# Devi_Lite.net
KiCad netlist of a schematic drawn in EAGLE
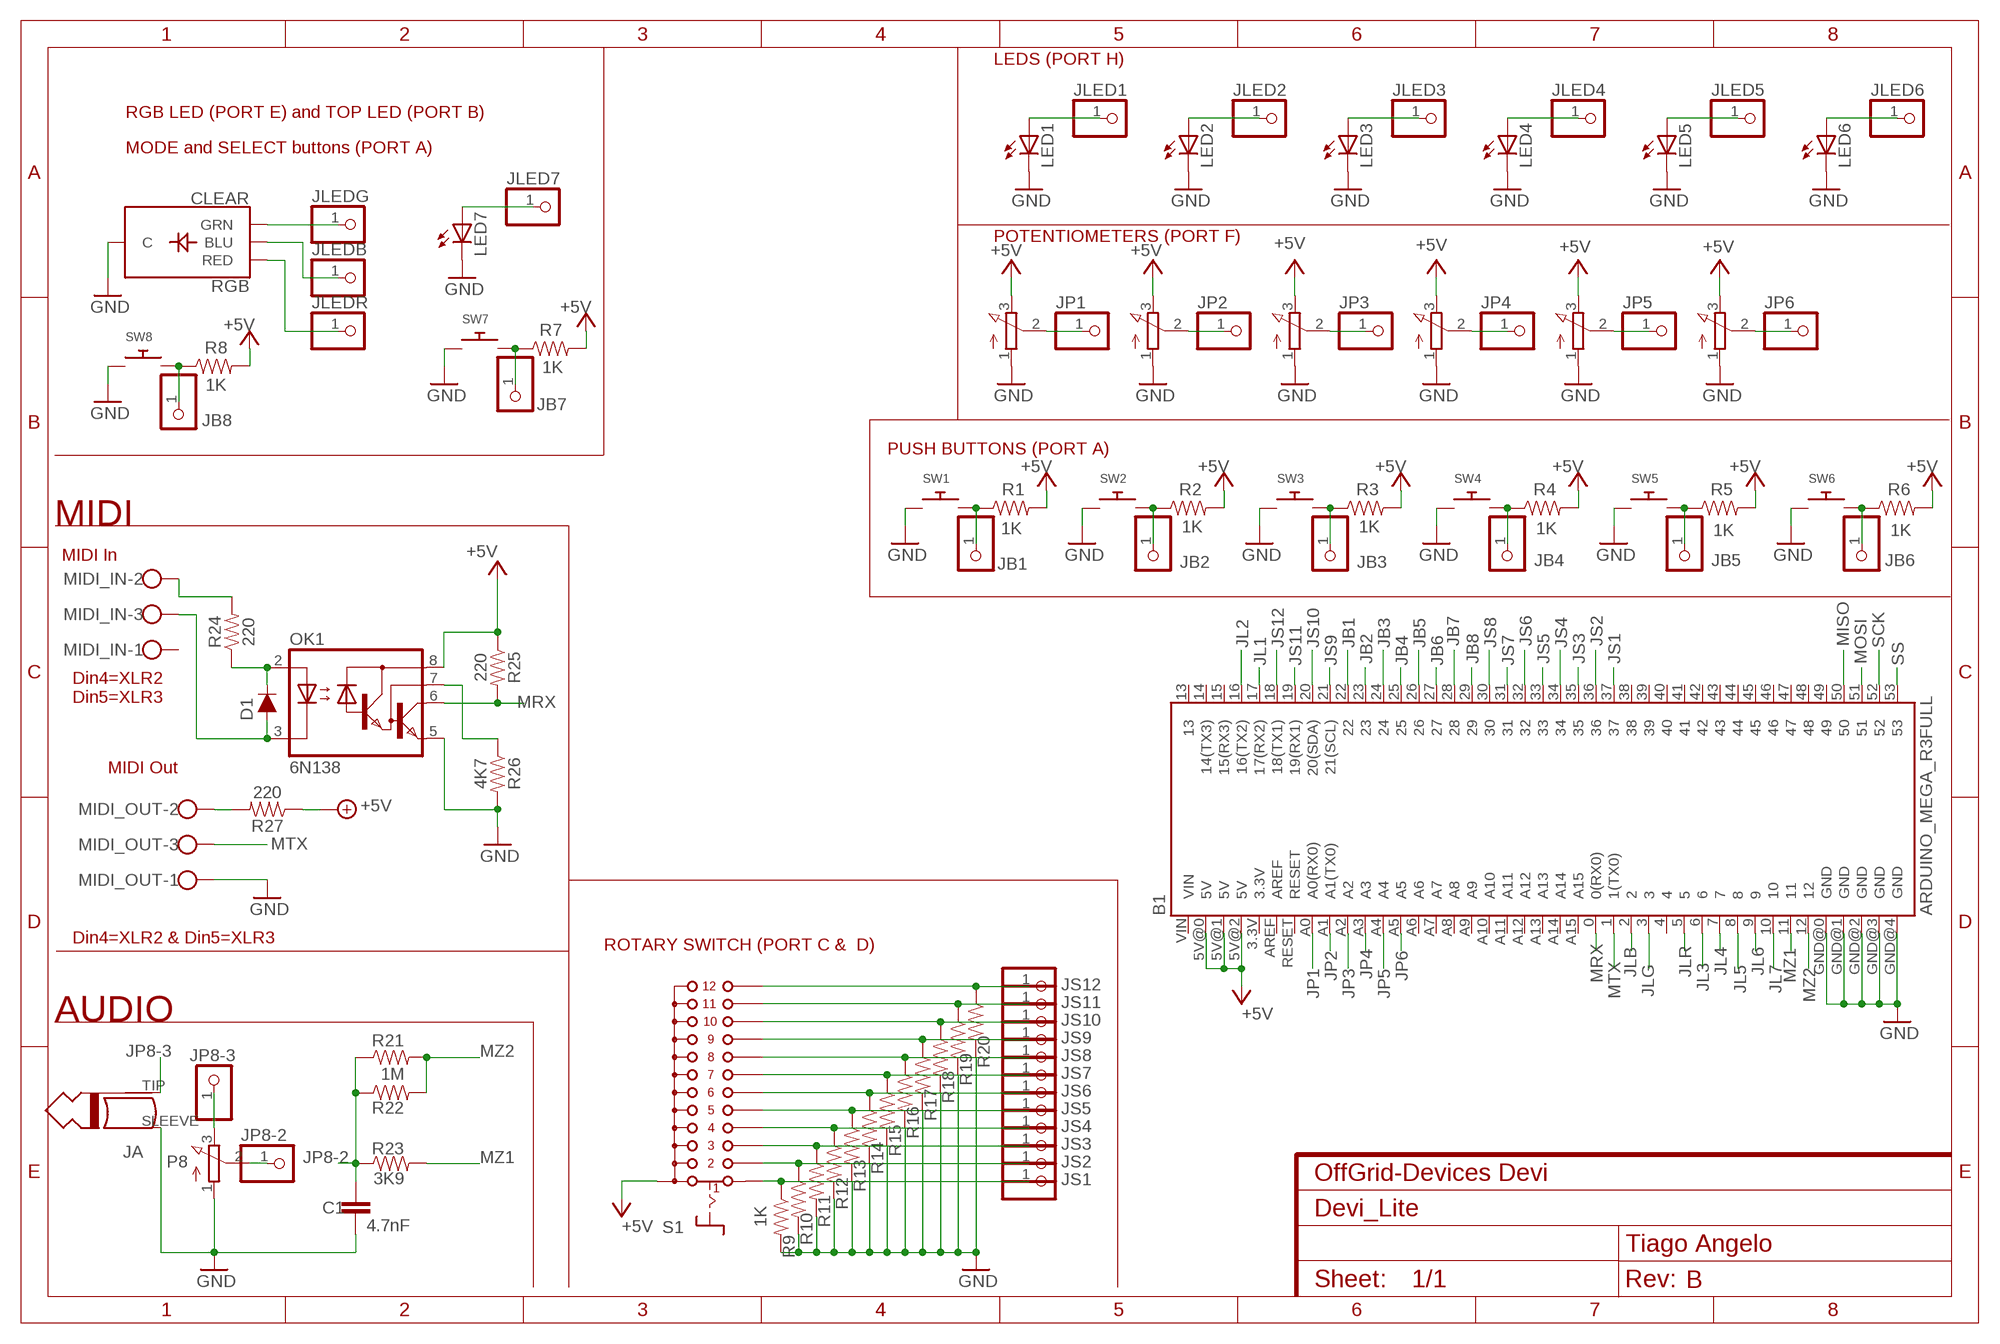
[diagram p0: schematic, sheet 1]

(export (version "E")
  (design (tool "Eeschema 10.0.6"))
  (components
    (comp (ref "B1")
      (value "ARDUINO_MEGA_R3FULL")
      (footprint "eagle-import:ARDUINO_MEGA")
      (libsource (lib "eagle-import") (part "ARDUINO_MEGA_R3FULL"))
    )
    (comp (ref "C1")
      (value "4.7nF")
      (footprint "eagle-import:C050-025X075")
      (libsource (lib "eagle-import") (part "C-EU050-025X075"))
    )
    (comp (ref "D1")
      (value "200mA/100V/1V")
      (footprint "eagle-import:DIODE-1N4148")
      (libsource (lib "eagle-import") (part "DIODE-1N4148"))
    )
    (comp (ref "JA")
      (value "MONO_PLUG")
      (footprint "eagle-import:TWO_PADS")
      (libsource (lib "eagle-import") (part "MONO_PLUG"))
    )
    (comp (ref "JB1")
      (value "PINHD-1X1CB")
      (footprint "eagle-import:1X01-CLEANBIG")
      (libsource (lib "eagle-import") (part "PINHD-1X1CB"))
    )
    (comp (ref "JB2")
      (value "PINHD-1X1CB")
      (footprint "eagle-import:1X01-CLEANBIG")
      (libsource (lib "eagle-import") (part "PINHD-1X1CB"))
    )
    (comp (ref "JB3")
      (value "PINHD-1X1CB")
      (footprint "eagle-import:1X01-CLEANBIG")
      (libsource (lib "eagle-import") (part "PINHD-1X1CB"))
    )
    (comp (ref "JB4")
      (value "PINHD-1X1CB")
      (footprint "eagle-import:1X01-CLEANBIG")
      (libsource (lib "eagle-import") (part "PINHD-1X1CB"))
    )
    (comp (ref "JB5")
      (value "PINHD-1X1CB")
      (footprint "eagle-import:1X01-CLEANBIG")
      (libsource (lib "eagle-import") (part "PINHD-1X1CB"))
    )
    (comp (ref "JB6")
      (value "PINHD-1X1CB")
      (footprint "eagle-import:1X01-CLEANBIG")
      (libsource (lib "eagle-import") (part "PINHD-1X1CB"))
    )
    (comp (ref "JB7")
      (value "PINHD-1X1CB")
      (footprint "eagle-import:1X01-CLEANBIG")
      (libsource (lib "eagle-import") (part "PINHD-1X1CB"))
    )
    (comp (ref "JB8")
      (value "PINHD-1X1CB")
      (footprint "eagle-import:1X01-CLEANBIG")
      (libsource (lib "eagle-import") (part "PINHD-1X1CB"))
    )
    (comp (ref "JLED1")
      (value "PINHD-1X1CB")
      (footprint "eagle-import:1X01-CLEANBIG")
      (libsource (lib "eagle-import") (part "PINHD-1X1CB"))
    )
    (comp (ref "JLED2")
      (value "PINHD-1X1CB")
      (footprint "eagle-import:1X01-CLEANBIG")
      (libsource (lib "eagle-import") (part "PINHD-1X1CB"))
    )
    (comp (ref "JLED3")
      (value "PINHD-1X1CB")
      (footprint "eagle-import:1X01-CLEANBIG")
      (libsource (lib "eagle-import") (part "PINHD-1X1CB"))
    )
    (comp (ref "JLED4")
      (value "PINHD-1X1CB")
      (footprint "eagle-import:1X01-CLEANBIG")
      (libsource (lib "eagle-import") (part "PINHD-1X1CB"))
    )
    (comp (ref "JLED5")
      (value "PINHD-1X1CB")
      (footprint "eagle-import:1X01-CLEANBIG")
      (libsource (lib "eagle-import") (part "PINHD-1X1CB"))
    )
    (comp (ref "JLED6")
      (value "PINHD-1X1CB")
      (footprint "eagle-import:1X01-CLEANBIG")
      (libsource (lib "eagle-import") (part "PINHD-1X1CB"))
    )
    (comp (ref "JLED7")
      (value "PINHD-1X1CB")
      (footprint "eagle-import:1X01-CLEANBIG")
      (libsource (lib "eagle-import") (part "PINHD-1X1CB"))
    )
    (comp (ref "JLEDB")
      (value "PINHD-1X1CB")
      (footprint "eagle-import:1X01-CLEANBIG")
      (libsource (lib "eagle-import") (part "PINHD-1X1CB"))
    )
    (comp (ref "JLEDG")
      (value "PINHD-1X1CB")
      (footprint "eagle-import:1X01-CLEANBIG")
      (libsource (lib "eagle-import") (part "PINHD-1X1CB"))
    )
    (comp (ref "JLEDR")
      (value "PINHD-1X1CB")
      (footprint "eagle-import:1X01-CLEANBIG")
      (libsource (lib "eagle-import") (part "PINHD-1X1CB"))
    )
    (comp (ref "JP1")
      (value "PINHD-1X1CB")
      (footprint "eagle-import:1X01-CLEANBIG")
      (libsource (lib "eagle-import") (part "PINHD-1X1CB"))
    )
    (comp (ref "JP2")
      (value "PINHD-1X1CB")
      (footprint "eagle-import:1X01-CLEANBIG")
      (libsource (lib "eagle-import") (part "PINHD-1X1CB"))
    )
    (comp (ref "JP3")
      (value "PINHD-1X1CB")
      (footprint "eagle-import:1X01-CLEANBIG")
      (libsource (lib "eagle-import") (part "PINHD-1X1CB"))
    )
    (comp (ref "JP4")
      (value "PINHD-1X1CB")
      (footprint "eagle-import:1X01-CLEANBIG")
      (libsource (lib "eagle-import") (part "PINHD-1X1CB"))
    )
    (comp (ref "JP5")
      (value "PINHD-1X1CB")
      (footprint "eagle-import:1X01-CLEANBIG")
      (libsource (lib "eagle-import") (part "PINHD-1X1CB"))
    )
    (comp (ref "JP6")
      (value "PINHD-1X1CB")
      (footprint "eagle-import:1X01-CLEANBIG")
      (libsource (lib "eagle-import") (part "PINHD-1X1CB"))
    )
    (comp (ref "JP8-2")
      (value "PINHD-1X1CB")
      (footprint "eagle-import:1X01-CLEANBIG")
      (libsource (lib "eagle-import") (part "PINHD-1X1CB"))
    )
    (comp (ref "JP8-3")
      (value "PINHD-1X1CB")
      (footprint "eagle-import:1X01-CLEANBIG")
      (libsource (lib "eagle-import") (part "PINHD-1X1CB"))
    )
    (comp (ref "JS1")
      (value "PINHD-1X1CB")
      (footprint "eagle-import:1X01-CLEANBIG")
      (libsource (lib "eagle-import") (part "PINHD-1X1CB"))
    )
    (comp (ref "JS2")
      (value "PINHD-1X1CB")
      (footprint "eagle-import:1X01-CLEANBIG")
      (libsource (lib "eagle-import") (part "PINHD-1X1CB"))
    )
    (comp (ref "JS3")
      (value "PINHD-1X1CB")
      (footprint "eagle-import:1X01-CLEANBIG")
      (libsource (lib "eagle-import") (part "PINHD-1X1CB"))
    )
    (comp (ref "JS4")
      (value "PINHD-1X1CB")
      (footprint "eagle-import:1X01-CLEANBIG")
      (libsource (lib "eagle-import") (part "PINHD-1X1CB"))
    )
    (comp (ref "JS5")
      (value "PINHD-1X1CB")
      (footprint "eagle-import:1X01-CLEANBIG")
      (libsource (lib "eagle-import") (part "PINHD-1X1CB"))
    )
    (comp (ref "JS6")
      (value "PINHD-1X1CB")
      (footprint "eagle-import:1X01-CLEANBIG")
      (libsource (lib "eagle-import") (part "PINHD-1X1CB"))
    )
    (comp (ref "JS7")
      (value "PINHD-1X1CB")
      (footprint "eagle-import:1X01-CLEANBIG")
      (libsource (lib "eagle-import") (part "PINHD-1X1CB"))
    )
    (comp (ref "JS8")
      (value "PINHD-1X1CB")
      (footprint "eagle-import:1X01-CLEANBIG")
      (libsource (lib "eagle-import") (part "PINHD-1X1CB"))
    )
    (comp (ref "JS9")
      (value "PINHD-1X1CB")
      (footprint "eagle-import:1X01-CLEANBIG")
      (libsource (lib "eagle-import") (part "PINHD-1X1CB"))
    )
    (comp (ref "JS10")
      (value "PINHD-1X1CB")
      (footprint "eagle-import:1X01-CLEANBIG")
      (libsource (lib "eagle-import") (part "PINHD-1X1CB"))
    )
    (comp (ref "JS11")
      (value "PINHD-1X1CB")
      (footprint "eagle-import:1X01-CLEANBIG")
      (libsource (lib "eagle-import") (part "PINHD-1X1CB"))
    )
    (comp (ref "JS12")
      (value "PINHD-1X1CB")
      (footprint "eagle-import:1X01-CLEANBIG")
      (libsource (lib "eagle-import") (part "PINHD-1X1CB"))
    )
    (comp (ref "LED1")
      (value "LED3MM")
      (footprint "eagle-import:LED3MM")
      (libsource (lib "eagle-import") (part "LED3MM"))
    )
    (comp (ref "LED2")
      (value "LED3MM")
      (footprint "eagle-import:LED3MM")
      (libsource (lib "eagle-import") (part "LED3MM"))
    )
    (comp (ref "LED3")
      (value "LED3MM")
      (footprint "eagle-import:LED3MM")
      (libsource (lib "eagle-import") (part "LED3MM"))
    )
    (comp (ref "LED4")
      (value "LED3MM")
      (footprint "eagle-import:LED3MM")
      (libsource (lib "eagle-import") (part "LED3MM"))
    )
    (comp (ref "LED5")
      (value "LED3MM")
      (footprint "eagle-import:LED3MM")
      (libsource (lib "eagle-import") (part "LED3MM"))
    )
    (comp (ref "LED6")
      (value "LED3MM")
      (footprint "eagle-import:LED3MM")
      (libsource (lib "eagle-import") (part "LED3MM"))
    )
    (comp (ref "LED7")
      (value "LED3MM")
      (footprint "eagle-import:LED3MM")
      (libsource (lib "eagle-import") (part "LED3MM"))
    )
    (comp (ref "MIDI_IN")
      (value "W237-103")
      (footprint "eagle-import:W237-103")
      (fields (field (name "MPN") "237-103"))
      (libsource (lib "eagle-import") (part "W237-103"))
    )
    (comp (ref "MIDI_OUT")
      (value "W237-103")
      (footprint "eagle-import:W237-103")
      (fields (field (name "MPN") "237-103"))
      (libsource (lib "eagle-import") (part "W237-103"))
    )
    (comp (ref "OK1")
      (value "6N138")
      (footprint "eagle-import:DIL08")
      (fields (field (name "MF") "VISHAY/TELEFUNKEN"))
      (libsource (lib "eagle-import") (part "6N138"))
    )
    (comp (ref "P1")
      (value "3RP/1610N")
      (footprint "eagle-import:3RP_1610N")
      (libsource (lib "eagle-import") (part "3RP/1610N"))
    )
    (comp (ref "P2")
      (value "3RP/1610N")
      (footprint "eagle-import:3RP_1610N")
      (libsource (lib "eagle-import") (part "3RP/1610N"))
    )
    (comp (ref "P3")
      (value "3RP/1610N")
      (footprint "eagle-import:3RP_1610N")
      (libsource (lib "eagle-import") (part "3RP/1610N"))
    )
    (comp (ref "P4")
      (value "3RP/1610N")
      (footprint "eagle-import:3RP_1610N")
      (libsource (lib "eagle-import") (part "3RP/1610N"))
    )
    (comp (ref "P5")
      (value "3RP/1610N")
      (footprint "eagle-import:3RP_1610N")
      (libsource (lib "eagle-import") (part "3RP/1610N"))
    )
    (comp (ref "P6")
      (value "3RP/1610N")
      (footprint "eagle-import:3RP_1610N")
      (libsource (lib "eagle-import") (part "3RP/1610N"))
    )
    (comp (ref "P8")
      (value "3RP/1610N")
      (footprint "eagle-import:3RP_1610N")
      (libsource (lib "eagle-import") (part "3RP/1610N"))
    )
    (comp (ref "R1")
      (value "1K")
      (footprint "eagle-import:AXIAL-0.3")
      (libsource (lib "eagle-import") (part "1KOHM-HORIZ-1/4W-5%"))
    )
    (comp (ref "R2")
      (value "1K")
      (footprint "eagle-import:AXIAL-0.3")
      (libsource (lib "eagle-import") (part "1KOHM-HORIZ-1/4W-5%"))
    )
    (comp (ref "R3")
      (value "1K")
      (footprint "eagle-import:AXIAL-0.3")
      (libsource (lib "eagle-import") (part "1KOHM-HORIZ-1/4W-5%"))
    )
    (comp (ref "R4")
      (value "1K")
      (footprint "eagle-import:AXIAL-0.3")
      (libsource (lib "eagle-import") (part "1KOHM-HORIZ-1/4W-5%"))
    )
    (comp (ref "R5")
      (value "1K")
      (footprint "eagle-import:AXIAL-0.3")
      (libsource (lib "eagle-import") (part "1KOHM-HORIZ-1/4W-5%"))
    )
    (comp (ref "R6")
      (value "1K")
      (footprint "eagle-import:AXIAL-0.3")
      (libsource (lib "eagle-import") (part "1KOHM-HORIZ-1/4W-5%"))
    )
    (comp (ref "R7")
      (value "1K")
      (footprint "eagle-import:AXIAL-0.3")
      (libsource (lib "eagle-import") (part "1KOHM-HORIZ-1/4W-5%"))
    )
    (comp (ref "R8")
      (value "1K")
      (footprint "eagle-import:AXIAL-0.3")
      (libsource (lib "eagle-import") (part "1KOHM-HORIZ-1/4W-5%"))
    )
    (comp (ref "R9")
      (value "1K")
      (footprint "eagle-import:AXIAL-0.3")
      (libsource (lib "eagle-import") (part "1KOHM-HORIZ-1/4W-5%"))
    )
    (comp (ref "R10")
      (value "1K")
      (footprint "eagle-import:AXIAL-0.3")
      (libsource (lib "eagle-import") (part "1KOHM-HORIZ-1/4W-5%"))
    )
    (comp (ref "R11")
      (value "1K")
      (footprint "eagle-import:AXIAL-0.3")
      (libsource (lib "eagle-import") (part "1KOHM-HORIZ-1/4W-5%"))
    )
    (comp (ref "R12")
      (value "1K")
      (footprint "eagle-import:AXIAL-0.3")
      (libsource (lib "eagle-import") (part "1KOHM-HORIZ-1/4W-5%"))
    )
    (comp (ref "R13")
      (value "1K")
      (footprint "eagle-import:AXIAL-0.3")
      (libsource (lib "eagle-import") (part "1KOHM-HORIZ-1/4W-5%"))
    )
    (comp (ref "R14")
      (value "1K")
      (footprint "eagle-import:AXIAL-0.3")
      (libsource (lib "eagle-import") (part "1KOHM-HORIZ-1/4W-5%"))
    )
    (comp (ref "R15")
      (value "1K")
      (footprint "eagle-import:AXIAL-0.3")
      (libsource (lib "eagle-import") (part "1KOHM-HORIZ-1/4W-5%"))
    )
    (comp (ref "R16")
      (value "1K")
      (footprint "eagle-import:AXIAL-0.3")
      (libsource (lib "eagle-import") (part "1KOHM-HORIZ-1/4W-5%"))
    )
    (comp (ref "R17")
      (value "1K")
      (footprint "eagle-import:AXIAL-0.3")
      (libsource (lib "eagle-import") (part "1KOHM-HORIZ-1/4W-5%"))
    )
    (comp (ref "R18")
      (value "1K")
      (footprint "eagle-import:AXIAL-0.3")
      (libsource (lib "eagle-import") (part "1KOHM-HORIZ-1/4W-5%"))
    )
    (comp (ref "R19")
      (value "1K")
      (footprint "eagle-import:AXIAL-0.3")
      (libsource (lib "eagle-import") (part "1KOHM-HORIZ-1/4W-5%"))
    )
    (comp (ref "R20")
      (value "1K")
      (footprint "eagle-import:AXIAL-0.3")
      (libsource (lib "eagle-import") (part "1KOHM-HORIZ-1/4W-5%"))
    )
    (comp (ref "R21")
      (value "1M")
      (footprint "eagle-import:AXIAL-0.3")
      (libsource (lib "eagle-import") (part "1KOHM-HORIZ-1/4W-5%"))
    )
    (comp (ref "R22")
      (value "1M")
      (footprint "eagle-import:AXIAL-0.3")
      (libsource (lib "eagle-import") (part "1KOHM-HORIZ-1/4W-5%"))
    )
    (comp (ref "R23")
      (value "3K9")
      (footprint "eagle-import:AXIAL-0.3")
      (libsource (lib "eagle-import") (part "1KOHM-HORIZ-1/4W-5%"))
    )
    (comp (ref "R24")
      (value "220")
      (footprint "eagle-import:AXIAL-0.3")
      (libsource (lib "eagle-import") (part "1KOHM-HORIZ-1/4W-5%"))
    )
    (comp (ref "R25")
      (value "220")
      (footprint "eagle-import:AXIAL-0.3")
      (libsource (lib "eagle-import") (part "1KOHM-HORIZ-1/4W-5%"))
    )
    (comp (ref "R26")
      (value "4K7")
      (footprint "eagle-import:AXIAL-0.3")
      (libsource (lib "eagle-import") (part "1KOHM-HORIZ-1/4W-5%"))
    )
    (comp (ref "R27")
      (value "220")
      (footprint "eagle-import:AXIAL-0.3")
      (libsource (lib "eagle-import") (part "1KOHM-HORIZ-1/4W-5%"))
    )
    (comp (ref "RGB")
      (value "CLEAR")
      (footprint "eagle-import:LED-RGB-THRU")
      (libsource (lib "eagle-import") (part "LED-RGB-CCCLEAR"))
    )
    (comp (ref "S1")
      (value "CK101X12")
      (footprint "eagle-import:CK101X12")
      (libsource (lib "eagle-import") (part "CK101X12"))
    )
    (comp (ref "SW1")
      (value "SWITCH_PUSHBUTTONEVQ-PE")
      (footprint "eagle-import:TACT_PANA-EVQ")
      (libsource (lib "eagle-import") (part "SWITCH_PUSHBUTTONEVQ-PE"))
    )
    (comp (ref "SW2")
      (value "SWITCH_PUSHBUTTONEVQ-PE")
      (footprint "eagle-import:TACT_PANA-EVQ")
      (libsource (lib "eagle-import") (part "SWITCH_PUSHBUTTONEVQ-PE"))
    )
    (comp (ref "SW3")
      (value "SWITCH_PUSHBUTTONEVQ-PE")
      (footprint "eagle-import:TACT_PANA-EVQ")
      (libsource (lib "eagle-import") (part "SWITCH_PUSHBUTTONEVQ-PE"))
    )
    (comp (ref "SW4")
      (value "SWITCH_PUSHBUTTONEVQ-PE")
      (footprint "eagle-import:TACT_PANA-EVQ")
      (libsource (lib "eagle-import") (part "SWITCH_PUSHBUTTONEVQ-PE"))
    )
    (comp (ref "SW5")
      (value "SWITCH_PUSHBUTTONEVQ-PE")
      (footprint "eagle-import:TACT_PANA-EVQ")
      (libsource (lib "eagle-import") (part "SWITCH_PUSHBUTTONEVQ-PE"))
    )
    (comp (ref "SW6")
      (value "SWITCH_PUSHBUTTONEVQ-PE")
      (footprint "eagle-import:TACT_PANA-EVQ")
      (libsource (lib "eagle-import") (part "SWITCH_PUSHBUTTONEVQ-PE"))
    )
    (comp (ref "SW7")
      (value "SWITCH_PUSHBUTTONEVQ-PE")
      (footprint "eagle-import:TACT_PANA-EVQ")
      (libsource (lib "eagle-import") (part "SWITCH_PUSHBUTTONEVQ-PE"))
    )
    (comp (ref "SW8")
      (value "SWITCH_PUSHBUTTONEVQ-PE")
      (footprint "eagle-import:TACT_PANA-EVQ")
      (libsource (lib "eagle-import") (part "SWITCH_PUSHBUTTONEVQ-PE"))
    )
  )
  (nets
    (net (code "1") (name "+5V") (class "Default")
      (node (ref "B1") (pin "5V@0") (pinfunction "5V_5V@0") (pintype "bidirectional"))
      (node (ref "B1") (pin "5V@1") (pinfunction "5V_5V@1") (pintype "bidirectional"))
      (node (ref "B1") (pin "5V@2") (pinfunction "5V_5V@2") (pintype "bidirectional"))
      (node (ref "OK1") (pin "8") (pinfunction "VCC_8") (pintype "passive"))
      (node (ref "P1") (pin "3") (pinfunction "E_3") (pintype "passive"))
      (node (ref "P2") (pin "3") (pinfunction "E_3") (pintype "passive"))
      (node (ref "P3") (pin "3") (pinfunction "E_3") (pintype "passive"))
      (node (ref "P4") (pin "3") (pinfunction "E_3") (pintype "passive"))
      (node (ref "P5") (pin "3") (pinfunction "E_3") (pintype "passive"))
      (node (ref "P6") (pin "3") (pinfunction "E_3") (pintype "passive"))
      (node (ref "R1") (pin "P$2") (pinfunction "2_P$2") (pintype "passive"))
      (node (ref "R2") (pin "P$2") (pinfunction "2_P$2") (pintype "passive"))
      (node (ref "R25") (pin "P$1") (pinfunction "1_P$1") (pintype "passive"))
      (node (ref "R27") (pin "P$1") (pinfunction "1_P$1") (pintype "passive"))
      (node (ref "R3") (pin "P$2") (pinfunction "2_P$2") (pintype "passive"))
      (node (ref "R4") (pin "P$2") (pinfunction "2_P$2") (pintype "passive"))
      (node (ref "R5") (pin "P$2") (pinfunction "2_P$2") (pintype "passive"))
      (node (ref "R6") (pin "P$2") (pinfunction "2_P$2") (pintype "passive"))
      (node (ref "R7") (pin "P$2") (pinfunction "2_P$2") (pintype "passive"))
      (node (ref "R8") (pin "P$2") (pinfunction "2_P$2") (pintype "passive"))
      (node (ref "S1") (pin "A") (pinfunction "A_A") (pintype "passive"))
    )
    (net (code "2") (name "/JB1") (class "Default")
      (node (ref "B1") (pin "22") (pinfunction "22_22") (pintype "bidirectional"))
      (node (ref "JB1") (pin "1") (pinfunction "1_1") (pintype "passive"))
      (node (ref "R1") (pin "P$1") (pinfunction "1_P$1") (pintype "passive"))
      (node (ref "SW1") (pin "P$2") (pinfunction "P$2_P$2") (pintype "passive"))
    )
    (net (code "3") (name "/JB2") (class "Default")
      (node (ref "B1") (pin "23") (pinfunction "23_23") (pintype "bidirectional"))
      (node (ref "JB2") (pin "1") (pinfunction "1_1") (pintype "passive"))
      (node (ref "R2") (pin "P$1") (pinfunction "1_P$1") (pintype "passive"))
      (node (ref "SW2") (pin "P$2") (pinfunction "P$2_P$2") (pintype "passive"))
    )
    (net (code "4") (name "/JB3") (class "Default")
      (node (ref "B1") (pin "24") (pinfunction "24_24") (pintype "bidirectional"))
      (node (ref "JB3") (pin "1") (pinfunction "1_1") (pintype "passive"))
      (node (ref "R3") (pin "P$1") (pinfunction "1_P$1") (pintype "passive"))
      (node (ref "SW3") (pin "P$2") (pinfunction "P$2_P$2") (pintype "passive"))
    )
    (net (code "5") (name "/JB4") (class "Default")
      (node (ref "B1") (pin "25") (pinfunction "25_25") (pintype "bidirectional"))
      (node (ref "JB4") (pin "1") (pinfunction "1_1") (pintype "passive"))
      (node (ref "R4") (pin "P$1") (pinfunction "1_P$1") (pintype "passive"))
      (node (ref "SW4") (pin "P$2") (pinfunction "P$2_P$2") (pintype "passive"))
    )
    (net (code "6") (name "/JB5") (class "Default")
      (node (ref "B1") (pin "26") (pinfunction "26_26") (pintype "bidirectional"))
      (node (ref "JB5") (pin "1") (pinfunction "1_1") (pintype "passive"))
      (node (ref "R5") (pin "P$1") (pinfunction "1_P$1") (pintype "passive"))
      (node (ref "SW5") (pin "P$2") (pinfunction "P$2_P$2") (pintype "passive"))
    )
    (net (code "7") (name "/JB6") (class "Default")
      (node (ref "B1") (pin "27") (pinfunction "27_27") (pintype "bidirectional"))
      (node (ref "JB6") (pin "1") (pinfunction "1_1") (pintype "passive"))
      (node (ref "R6") (pin "P$1") (pinfunction "1_P$1") (pintype "passive"))
      (node (ref "SW6") (pin "P$2") (pinfunction "P$2_P$2") (pintype "passive"))
    )
    (net (code "8") (name "/JB7") (class "Default")
      (node (ref "B1") (pin "28") (pinfunction "28_28") (pintype "bidirectional"))
      (node (ref "JB7") (pin "1") (pinfunction "1_1") (pintype "passive"))
      (node (ref "R7") (pin "P$1") (pinfunction "1_P$1") (pintype "passive"))
      (node (ref "SW7") (pin "P$2") (pinfunction "P$2_P$2") (pintype "passive"))
    )
    (net (code "9") (name "/JB8") (class "Default")
      (node (ref "B1") (pin "29") (pinfunction "29_29") (pintype "bidirectional"))
      (node (ref "JB8") (pin "1") (pinfunction "1_1") (pintype "passive"))
      (node (ref "R8") (pin "P$1") (pinfunction "1_P$1") (pintype "passive"))
      (node (ref "SW8") (pin "P$2") (pinfunction "P$2_P$2") (pintype "passive"))
    )
    (net (code "10") (name "/JL1") (class "Default")
      (node (ref "B1") (pin "17") (pinfunction "17(RX2)_17") (pintype "bidirectional"))
      (node (ref "JLED1") (pin "1") (pinfunction "1_1") (pintype "passive"))
      (node (ref "LED1") (pin "A") (pinfunction "A_A") (pintype "passive"))
    )
    (net (code "11") (name "/JL2") (class "Default")
      (node (ref "B1") (pin "16") (pinfunction "16(TX2)_16") (pintype "bidirectional"))
      (node (ref "JLED2") (pin "1") (pinfunction "1_1") (pintype "passive"))
      (node (ref "LED2") (pin "A") (pinfunction "A_A") (pintype "passive"))
    )
    (net (code "12") (name "/JL3") (class "Default")
      (node (ref "B1") (pin "6") (pinfunction "6_6") (pintype "bidirectional"))
      (node (ref "JLED3") (pin "1") (pinfunction "1_1") (pintype "passive"))
      (node (ref "LED3") (pin "A") (pinfunction "A_A") (pintype "passive"))
    )
    (net (code "13") (name "/JL4") (class "Default")
      (node (ref "B1") (pin "7") (pinfunction "7_7") (pintype "bidirectional"))
      (node (ref "JLED4") (pin "1") (pinfunction "1_1") (pintype "passive"))
      (node (ref "LED4") (pin "A") (pinfunction "A_A") (pintype "passive"))
    )
    (net (code "14") (name "/JL5") (class "Default")
      (node (ref "B1") (pin "8") (pinfunction "8_8") (pintype "bidirectional"))
      (node (ref "JLED5") (pin "1") (pinfunction "1_1") (pintype "passive"))
      (node (ref "LED5") (pin "A") (pinfunction "A_A") (pintype "passive"))
    )
    (net (code "15") (name "/JL6") (class "Default")
      (node (ref "B1") (pin "9") (pinfunction "9_9") (pintype "bidirectional"))
      (node (ref "JLED6") (pin "1") (pinfunction "1_1") (pintype "passive"))
      (node (ref "LED6") (pin "A") (pinfunction "A_A") (pintype "passive"))
    )
    (net (code "16") (name "/JL7") (class "Default")
      (node (ref "B1") (pin "10") (pinfunction "10_10") (pintype "bidirectional"))
      (node (ref "JLED7") (pin "1") (pinfunction "1_1") (pintype "passive"))
      (node (ref "LED7") (pin "A") (pinfunction "A_A") (pintype "passive"))
    )
    (net (code "17") (name "/JLB") (class "Default")
      (node (ref "B1") (pin "2") (pinfunction "2_2") (pintype "bidirectional"))
      (node (ref "JLEDB") (pin "1") (pinfunction "1_1") (pintype "passive"))
      (node (ref "RGB") (pin "4") (pinfunction "BLU_4") (pintype "bidirectional"))
    )
    (net (code "18") (name "/JLG") (class "Default")
      (node (ref "B1") (pin "3") (pinfunction "3_3") (pintype "bidirectional"))
      (node (ref "JLEDG") (pin "1") (pinfunction "1_1") (pintype "passive"))
      (node (ref "RGB") (pin "3") (pinfunction "GRN_3") (pintype "bidirectional"))
    )
    (net (code "19") (name "/JLR") (class "Default")
      (node (ref "B1") (pin "5") (pinfunction "5_5") (pintype "bidirectional"))
      (node (ref "JLEDR") (pin "1") (pinfunction "1_1") (pintype "passive"))
      (node (ref "RGB") (pin "1") (pinfunction "RED_1") (pintype "bidirectional"))
    )
    (net (code "20") (name "/JP1") (class "Default")
      (node (ref "B1") (pin "A0") (pinfunction "A0(RX0)_A0") (pintype "bidirectional"))
      (node (ref "JP1") (pin "1") (pinfunction "1_1") (pintype "passive"))
      (node (ref "P1") (pin "2") (pinfunction "S_2") (pintype "passive"))
    )
    (net (code "21") (name "/JP2") (class "Default")
      (node (ref "B1") (pin "A1") (pinfunction "A1(TX0)_A1") (pintype "bidirectional"))
      (node (ref "JP2") (pin "1") (pinfunction "1_1") (pintype "passive"))
      (node (ref "P2") (pin "2") (pinfunction "S_2") (pintype "passive"))
    )
    (net (code "22") (name "/JP3") (class "Default")
      (node (ref "B1") (pin "A2") (pinfunction "A2_A2") (pintype "bidirectional"))
      (node (ref "JP3") (pin "1") (pinfunction "1_1") (pintype "passive"))
      (node (ref "P3") (pin "2") (pinfunction "S_2") (pintype "passive"))
    )
    (net (code "23") (name "/JP4") (class "Default")
      (node (ref "B1") (pin "A3") (pinfunction "A3_A3") (pintype "bidirectional"))
      (node (ref "JP4") (pin "1") (pinfunction "1_1") (pintype "passive"))
      (node (ref "P4") (pin "2") (pinfunction "S_2") (pintype "passive"))
    )
    (net (code "24") (name "/JP5") (class "Default")
      (node (ref "B1") (pin "A4") (pinfunction "A4_A4") (pintype "bidirectional"))
      (node (ref "JP5") (pin "1") (pinfunction "1_1") (pintype "passive"))
      (node (ref "P5") (pin "2") (pinfunction "S_2") (pintype "passive"))
    )
    (net (code "25") (name "/JP6") (class "Default")
      (node (ref "B1") (pin "A5") (pinfunction "A5_A5") (pintype "bidirectional"))
      (node (ref "JP6") (pin "1") (pinfunction "1_1") (pintype "passive"))
      (node (ref "P6") (pin "2") (pinfunction "S_2") (pintype "passive"))
    )
    (net (code "26") (name "/JP8-2") (class "Default")
      (node (ref "C1") (pin "1") (pinfunction "1_1") (pintype "passive"))
      (node (ref "JP8-2") (pin "1") (pinfunction "1_1") (pintype "passive"))
      (node (ref "P8") (pin "2") (pinfunction "S_2") (pintype "passive"))
      (node (ref "R21") (pin "P$1") (pinfunction "1_P$1") (pintype "passive"))
      (node (ref "R22") (pin "P$1") (pinfunction "1_P$1") (pintype "passive"))
      (node (ref "R23") (pin "P$1") (pinfunction "1_P$1") (pintype "passive"))
    )
    (net (code "27") (name "/JP8-3") (class "Default")
      (node (ref "JA") (pin "TIP") (pinfunction "TIP_TIP") (pintype "passive"))
      (node (ref "JP8-3") (pin "1") (pinfunction "1_1") (pintype "passive"))
      (node (ref "P8") (pin "3") (pinfunction "E_3") (pintype "passive"))
    )
    (net (code "28") (name "/JS1") (class "Default")
      (node (ref "B1") (pin "37") (pinfunction "37_37") (pintype "bidirectional"))
      (node (ref "JS1") (pin "1") (pinfunction "1_1") (pintype "passive"))
      (node (ref "R9") (pin "P$1") (pinfunction "1_P$1") (pintype "passive"))
      (node (ref "S1") (pin "1") (pinfunction "1_1") (pintype "passive"))
    )
    (net (code "29") (name "/JS2") (class "Default")
      (node (ref "B1") (pin "36") (pinfunction "36_36") (pintype "bidirectional"))
      (node (ref "JS2") (pin "1") (pinfunction "1_1") (pintype "passive"))
      (node (ref "R10") (pin "P$1") (pinfunction "1_P$1") (pintype "passive"))
      (node (ref "S1") (pin "2") (pinfunction "2_2") (pintype "passive"))
    )
    (net (code "30") (name "/JS3") (class "Default")
      (node (ref "B1") (pin "35") (pinfunction "35_35") (pintype "bidirectional"))
      (node (ref "JS3") (pin "1") (pinfunction "1_1") (pintype "passive"))
      (node (ref "R11") (pin "P$1") (pinfunction "1_P$1") (pintype "passive"))
      (node (ref "S1") (pin "3") (pinfunction "3_3") (pintype "passive"))
    )
    (net (code "31") (name "/JS4") (class "Default")
      (node (ref "B1") (pin "34") (pinfunction "34_34") (pintype "bidirectional"))
      (node (ref "JS4") (pin "1") (pinfunction "1_1") (pintype "passive"))
      (node (ref "R12") (pin "P$1") (pinfunction "1_P$1") (pintype "passive"))
      (node (ref "S1") (pin "4") (pinfunction "4_4") (pintype "passive"))
    )
    (net (code "32") (name "/JS5") (class "Default")
      (node (ref "B1") (pin "33") (pinfunction "33_33") (pintype "bidirectional"))
      (node (ref "JS5") (pin "1") (pinfunction "1_1") (pintype "passive"))
      (node (ref "R13") (pin "P$1") (pinfunction "1_P$1") (pintype "passive"))
      (node (ref "S1") (pin "5") (pinfunction "5_5") (pintype "passive"))
    )
    (net (code "33") (name "/JS6") (class "Default")
      (node (ref "B1") (pin "32") (pinfunction "32_32") (pintype "bidirectional"))
      (node (ref "JS6") (pin "1") (pinfunction "1_1") (pintype "passive"))
      (node (ref "R14") (pin "P$1") (pinfunction "1_P$1") (pintype "passive"))
      (node (ref "S1") (pin "6") (pinfunction "6_6") (pintype "passive"))
    )
    (net (code "34") (name "/JS7") (class "Default")
      (node (ref "B1") (pin "31") (pinfunction "31_31") (pintype "bidirectional"))
      (node (ref "JS7") (pin "1") (pinfunction "1_1") (pintype "passive"))
      (node (ref "R15") (pin "P$1") (pinfunction "1_P$1") (pintype "passive"))
      (node (ref "S1") (pin "7") (pinfunction "7_7") (pintype "passive"))
    )
    (net (code "35") (name "/JS8") (class "Default")
      (node (ref "B1") (pin "30") (pinfunction "30_30") (pintype "bidirectional"))
      (node (ref "JS8") (pin "1") (pinfunction "1_1") (pintype "passive"))
      (node (ref "R16") (pin "P$1") (pinfunction "1_P$1") (pintype "passive"))
      (node (ref "S1") (pin "8") (pinfunction "8_8") (pintype "passive"))
    )
    (net (code "36") (name "/JS9") (class "Default")
      (node (ref "B1") (pin "21") (pinfunction "21(SCL)_21") (pintype "bidirectional"))
      (node (ref "JS9") (pin "1") (pinfunction "1_1") (pintype "passive"))
      (node (ref "R17") (pin "P$1") (pinfunction "1_P$1") (pintype "passive"))
      (node (ref "S1") (pin "9") (pinfunction "9_9") (pintype "passive"))
    )
    (net (code "37") (name "/JS10") (class "Default")
      (node (ref "B1") (pin "20") (pinfunction "20(SDA)_20") (pintype "bidirectional"))
      (node (ref "JS10") (pin "1") (pinfunction "1_1") (pintype "passive"))
      (node (ref "R18") (pin "P$1") (pinfunction "1_P$1") (pintype "passive"))
      (node (ref "S1") (pin "10") (pinfunction "10_10") (pintype "passive"))
    )
    (net (code "38") (name "/JS11") (class "Default")
      (node (ref "B1") (pin "19") (pinfunction "19(RX1)_19") (pintype "bidirectional"))
      (node (ref "JS11") (pin "1") (pinfunction "1_1") (pintype "passive"))
      (node (ref "R19") (pin "P$1") (pinfunction "1_P$1") (pintype "passive"))
      (node (ref "S1") (pin "11") (pinfunction "11_11") (pintype "passive"))
    )
    (net (code "39") (name "/JS12") (class "Default")
      (node (ref "B1") (pin "18") (pinfunction "18(TX1)_18") (pintype "bidirectional"))
      (node (ref "JS12") (pin "1") (pinfunction "1_1") (pintype "passive"))
      (node (ref "R20") (pin "P$1") (pinfunction "1_P$1") (pintype "passive"))
      (node (ref "S1") (pin "12") (pinfunction "12_12") (pintype "passive"))
    )
    (net (code "40") (name "/MISO") (class "Default")
      (node (ref "B1") (pin "50") (pinfunction "50_50") (pintype "bidirectional"))
    )
    (net (code "41") (name "/MOSI") (class "Default")
      (node (ref "B1") (pin "51") (pinfunction "51_51") (pintype "bidirectional"))
    )
    (net (code "42") (name "/MRX") (class "Default")
      (node (ref "B1") (pin "0") (pinfunction "0(RX0)_0") (pintype "bidirectional"))
      (node (ref "OK1") (pin "6") (pinfunction "VO_6") (pintype "passive"))
      (node (ref "R25") (pin "P$2") (pinfunction "2_P$2") (pintype "passive"))
    )
    (net (code "43") (name "/MTX") (class "Default")
      (node (ref "B1") (pin "1") (pinfunction "1(TX0)_1") (pintype "bidirectional"))
      (node (ref "MIDI_OUT") (pin "3") (pinfunction "KL_3") (pintype "passive"))
    )
    (net (code "44") (name "/MZ1") (class "Default")
      (node (ref "B1") (pin "11") (pinfunction "11_11") (pintype "bidirectional"))
      (node (ref "R23") (pin "P$2") (pinfunction "2_P$2") (pintype "passive"))
    )
    (net (code "45") (name "/MZ2") (class "Default")
      (node (ref "B1") (pin "12") (pinfunction "12_12") (pintype "bidirectional"))
      (node (ref "R21") (pin "P$2") (pinfunction "2_P$2") (pintype "passive"))
      (node (ref "R22") (pin "P$2") (pinfunction "2_P$2") (pintype "passive"))
    )
    (net (code "46") (name "/SCK") (class "Default")
      (node (ref "B1") (pin "52") (pinfunction "52_52") (pintype "bidirectional"))
    )
    (net (code "47") (name "/SS") (class "Default")
      (node (ref "B1") (pin "53") (pinfunction "53_53") (pintype "bidirectional"))
    )
    (net (code "48") (name "GND") (class "Default")
      (node (ref "B1") (pin "GND@0") (pinfunction "GND_GND@0") (pintype "bidirectional"))
      (node (ref "B1") (pin "GND@1") (pinfunction "GND_GND@1") (pintype "bidirectional"))
      (node (ref "B1") (pin "GND@2") (pinfunction "GND_GND@2") (pintype "bidirectional"))
      (node (ref "B1") (pin "GND@3") (pinfunction "GND_GND@3") (pintype "bidirectional"))
      (node (ref "B1") (pin "GND@4") (pinfunction "GND_GND@4") (pintype "bidirectional"))
      (node (ref "C1") (pin "2") (pinfunction "2_2") (pintype "passive"))
      (node (ref "JA") (pin "SLEEVE") (pinfunction "SLEEVE_SLEEVE") (pintype "passive"))
      (node (ref "LED1") (pin "K") (pinfunction "C_K") (pintype "passive"))
      (node (ref "LED2") (pin "K") (pinfunction "C_K") (pintype "passive"))
      (node (ref "LED3") (pin "K") (pinfunction "C_K") (pintype "passive"))
      (node (ref "LED4") (pin "K") (pinfunction "C_K") (pintype "passive"))
      (node (ref "LED5") (pin "K") (pinfunction "C_K") (pintype "passive"))
      (node (ref "LED6") (pin "K") (pinfunction "C_K") (pintype "passive"))
      (node (ref "LED7") (pin "K") (pinfunction "C_K") (pintype "passive"))
      (node (ref "MIDI_OUT") (pin "1") (pinfunction "KL_1") (pintype "passive"))
      (node (ref "OK1") (pin "5") (pinfunction "GND_5") (pintype "passive"))
      (node (ref "P1") (pin "1") (pinfunction "A_1") (pintype "passive"))
      (node (ref "P2") (pin "1") (pinfunction "A_1") (pintype "passive"))
      (node (ref "P3") (pin "1") (pinfunction "A_1") (pintype "passive"))
      (node (ref "P4") (pin "1") (pinfunction "A_1") (pintype "passive"))
      (node (ref "P5") (pin "1") (pinfunction "A_1") (pintype "passive"))
      (node (ref "P6") (pin "1") (pinfunction "A_1") (pintype "passive"))
      (node (ref "P8") (pin "1") (pinfunction "A_1") (pintype "passive"))
      (node (ref "R10") (pin "P$2") (pinfunction "2_P$2") (pintype "passive"))
      (node (ref "R11") (pin "P$2") (pinfunction "2_P$2") (pintype "passive"))
      (node (ref "R12") (pin "P$2") (pinfunction "2_P$2") (pintype "passive"))
      (node (ref "R13") (pin "P$2") (pinfunction "2_P$2") (pintype "passive"))
      (node (ref "R14") (pin "P$2") (pinfunction "2_P$2") (pintype "passive"))
      (node (ref "R15") (pin "P$2") (pinfunction "2_P$2") (pintype "passive"))
      (node (ref "R16") (pin "P$2") (pinfunction "2_P$2") (pintype "passive"))
      (node (ref "R17") (pin "P$2") (pinfunction "2_P$2") (pintype "passive"))
      (node (ref "R18") (pin "P$2") (pinfunction "2_P$2") (pintype "passive"))
      (node (ref "R19") (pin "P$2") (pinfunction "2_P$2") (pintype "passive"))
      (node (ref "R20") (pin "P$2") (pinfunction "2_P$2") (pintype "passive"))
      (node (ref "R26") (pin "P$2") (pinfunction "2_P$2") (pintype "passive"))
      (node (ref "R9") (pin "P$2") (pinfunction "2_P$2") (pintype "passive"))
      (node (ref "RGB") (pin "2") (pinfunction "C_2") (pintype "bidirectional"))
      (node (ref "SW1") (pin "P$1") (pinfunction "P$1_P$1") (pintype "passive"))
      (node (ref "SW2") (pin "P$1") (pinfunction "P$1_P$1") (pintype "passive"))
      (node (ref "SW3") (pin "P$1") (pinfunction "P$1_P$1") (pintype "passive"))
      (node (ref "SW4") (pin "P$1") (pinfunction "P$1_P$1") (pintype "passive"))
      (node (ref "SW5") (pin "P$1") (pinfunction "P$1_P$1") (pintype "passive"))
      (node (ref "SW6") (pin "P$1") (pinfunction "P$1_P$1") (pintype "passive"))
      (node (ref "SW7") (pin "P$1") (pinfunction "P$1_P$1") (pintype "passive"))
      (node (ref "SW8") (pin "P$1") (pinfunction "P$1_P$1") (pintype "passive"))
    )
    (net (code "49") (name "Net-(MIDI_INB-KL)") (class "Default")
      (node (ref "MIDI_IN") (pin "2") (pinfunction "KL_2") (pintype "passive"))
      (node (ref "R24") (pin "P$2") (pinfunction "2_P$2") (pintype "passive"))
    )
    (net (code "50") (name "Net-(MIDI_INC-KL)") (class "Default")
      (node (ref "D1") (pin "A") (pinfunction "A_A") (pintype "passive"))
      (node (ref "MIDI_IN") (pin "3") (pinfunction "KL_3") (pintype "passive"))
      (node (ref "OK1") (pin "3") (pinfunction "C_3") (pintype "passive"))
    )
    (net (code "51") (name "Net-(MIDI_OUTB-KL)") (class "Default")
      (node (ref "MIDI_OUT") (pin "2") (pinfunction "KL_2") (pintype "passive"))
      (node (ref "R27") (pin "P$2") (pinfunction "2_P$2") (pintype "passive"))
    )
    (net (code "52") (name "Net-(OK1-A)") (class "Default")
      (node (ref "D1") (pin "C") (pinfunction "C_C") (pintype "passive"))
      (node (ref "OK1") (pin "2") (pinfunction "A_2") (pintype "passive"))
      (node (ref "R24") (pin "P$1") (pinfunction "1_P$1") (pintype "passive"))
    )
    (net (code "53") (name "Net-(OK1-VB)") (class "Default")
      (node (ref "OK1") (pin "7") (pinfunction "VB_7") (pintype "passive"))
      (node (ref "R26") (pin "P$1") (pinfunction "1_P$1") (pintype "passive"))
    )
    (net (code "54") (name "unconnected-(B1-14(TX3)-Pad14)") (class "Default")
      (node (ref "B1") (pin "14") (pinfunction "14(TX3)_14") (pintype "bidirectional"))
    )
    (net (code "55") (name "unconnected-(B1-15(RX3)-Pad15)") (class "Default")
      (node (ref "B1") (pin "15") (pinfunction "15(RX3)_15") (pintype "bidirectional"))
    )
    (net (code "56") (name "unconnected-(B1-Pad3.3V)") (class "Default")
      (node (ref "B1") (pin "3.3V") (pinfunction "3.3V_3.3V") (pintype "bidirectional"))
    )
    (net (code "57") (name "unconnected-(B1-Pad4)") (class "Default")
      (node (ref "B1") (pin "4") (pinfunction "4_4") (pintype "bidirectional"))
    )
    (net (code "58") (name "unconnected-(B1-Pad13)") (class "Default")
      (node (ref "B1") (pin "13") (pinfunction "13_13") (pintype "bidirectional"))
    )
    (net (code "59") (name "unconnected-(B1-Pad38)") (class "Default")
      (node (ref "B1") (pin "38") (pinfunction "38_38") (pintype "bidirectional"))
    )
    (net (code "60") (name "unconnected-(B1-Pad39)") (class "Default")
      (node (ref "B1") (pin "39") (pinfunction "39_39") (pintype "bidirectional"))
    )
    (net (code "61") (name "unconnected-(B1-Pad40)") (class "Default")
      (node (ref "B1") (pin "40") (pinfunction "40_40") (pintype "bidirectional"))
    )
    (net (code "62") (name "unconnected-(B1-Pad41)") (class "Default")
      (node (ref "B1") (pin "41") (pinfunction "41_41") (pintype "bidirectional"))
    )
    (net (code "63") (name "unconnected-(B1-Pad42)") (class "Default")
      (node (ref "B1") (pin "42") (pinfunction "42_42") (pintype "bidirectional"))
    )
    (net (code "64") (name "unconnected-(B1-Pad43)") (class "Default")
      (node (ref "B1") (pin "43") (pinfunction "43_43") (pintype "bidirectional"))
    )
    (net (code "65") (name "unconnected-(B1-Pad44)") (class "Default")
      (node (ref "B1") (pin "44") (pinfunction "44_44") (pintype "bidirectional"))
    )
    (net (code "66") (name "unconnected-(B1-Pad45)") (class "Default")
      (node (ref "B1") (pin "45") (pinfunction "45_45") (pintype "bidirectional"))
    )
    (net (code "67") (name "unconnected-(B1-Pad46)") (class "Default")
      (node (ref "B1") (pin "46") (pinfunction "46_46") (pintype "bidirectional"))
    )
    (net (code "68") (name "unconnected-(B1-Pad47)") (class "Default")
      (node (ref "B1") (pin "47") (pinfunction "47_47") (pintype "bidirectional"))
    )
    (net (code "69") (name "unconnected-(B1-Pad48)") (class "Default")
      (node (ref "B1") (pin "48") (pinfunction "48_48") (pintype "bidirectional"))
    )
    (net (code "70") (name "unconnected-(B1-Pad49)") (class "Default")
      (node (ref "B1") (pin "49") (pinfunction "49_49") (pintype "bidirectional"))
    )
    (net (code "71") (name "unconnected-(B1-PadA6)") (class "Default")
      (node (ref "B1") (pin "A6") (pinfunction "A6_A6") (pintype "bidirectional"))
    )
    (net (code "72") (name "unconnected-(B1-PadA7)") (class "Default")
      (node (ref "B1") (pin "A7") (pinfunction "A7_A7") (pintype "bidirectional"))
    )
    (net (code "73") (name "unconnected-(B1-PadA8)") (class "Default")
      (node (ref "B1") (pin "A8") (pinfunction "A8_A8") (pintype "bidirectional"))
    )
    (net (code "74") (name "unconnected-(B1-PadA9)") (class "Default")
      (node (ref "B1") (pin "A9") (pinfunction "A9_A9") (pintype "bidirectional"))
    )
    (net (code "75") (name "unconnected-(B1-PadA10)") (class "Default")
      (node (ref "B1") (pin "A10") (pinfunction "A10_A10") (pintype "bidirectional"))
    )
    (net (code "76") (name "unconnected-(B1-PadA11)") (class "Default")
      (node (ref "B1") (pin "A11") (pinfunction "A11_A11") (pintype "bidirectional"))
    )
    (net (code "77") (name "unconnected-(B1-PadA12)") (class "Default")
      (node (ref "B1") (pin "A12") (pinfunction "A12_A12") (pintype "bidirectional"))
    )
    (net (code "78") (name "unconnected-(B1-PadA13)") (class "Default")
      (node (ref "B1") (pin "A13") (pinfunction "A13_A13") (pintype "bidirectional"))
    )
    (net (code "79") (name "unconnected-(B1-PadA14)") (class "Default")
      (node (ref "B1") (pin "A14") (pinfunction "A14_A14") (pintype "bidirectional"))
    )
    (net (code "80") (name "unconnected-(B1-PadA15)") (class "Default")
      (node (ref "B1") (pin "A15") (pinfunction "A15_A15") (pintype "bidirectional"))
    )
    (net (code "81") (name "unconnected-(B1-PadAREF)") (class "Default")
      (node (ref "B1") (pin "AREF") (pinfunction "AREF_AREF") (pintype "bidirectional"))
    )
    (net (code "82") (name "unconnected-(B1-PadRESET)") (class "Default")
      (node (ref "B1") (pin "RESET") (pinfunction "RESET_RESET") (pintype "bidirectional"))
    )
    (net (code "83") (name "unconnected-(B1-PadVIN)") (class "Default")
      (node (ref "B1") (pin "VIN") (pinfunction "VIN_VIN") (pintype "bidirectional"))
    )
    (net (code "84") (name "unconnected-(MIDI_INA-KL-Pad1)") (class "Default")
      (node (ref "MIDI_IN") (pin "1") (pinfunction "KL_1") (pintype "passive"))
    )
  )
)
